# CCjammerRev2_TOP.net
KiCad netlist of a schematic drawn in Altium Designer
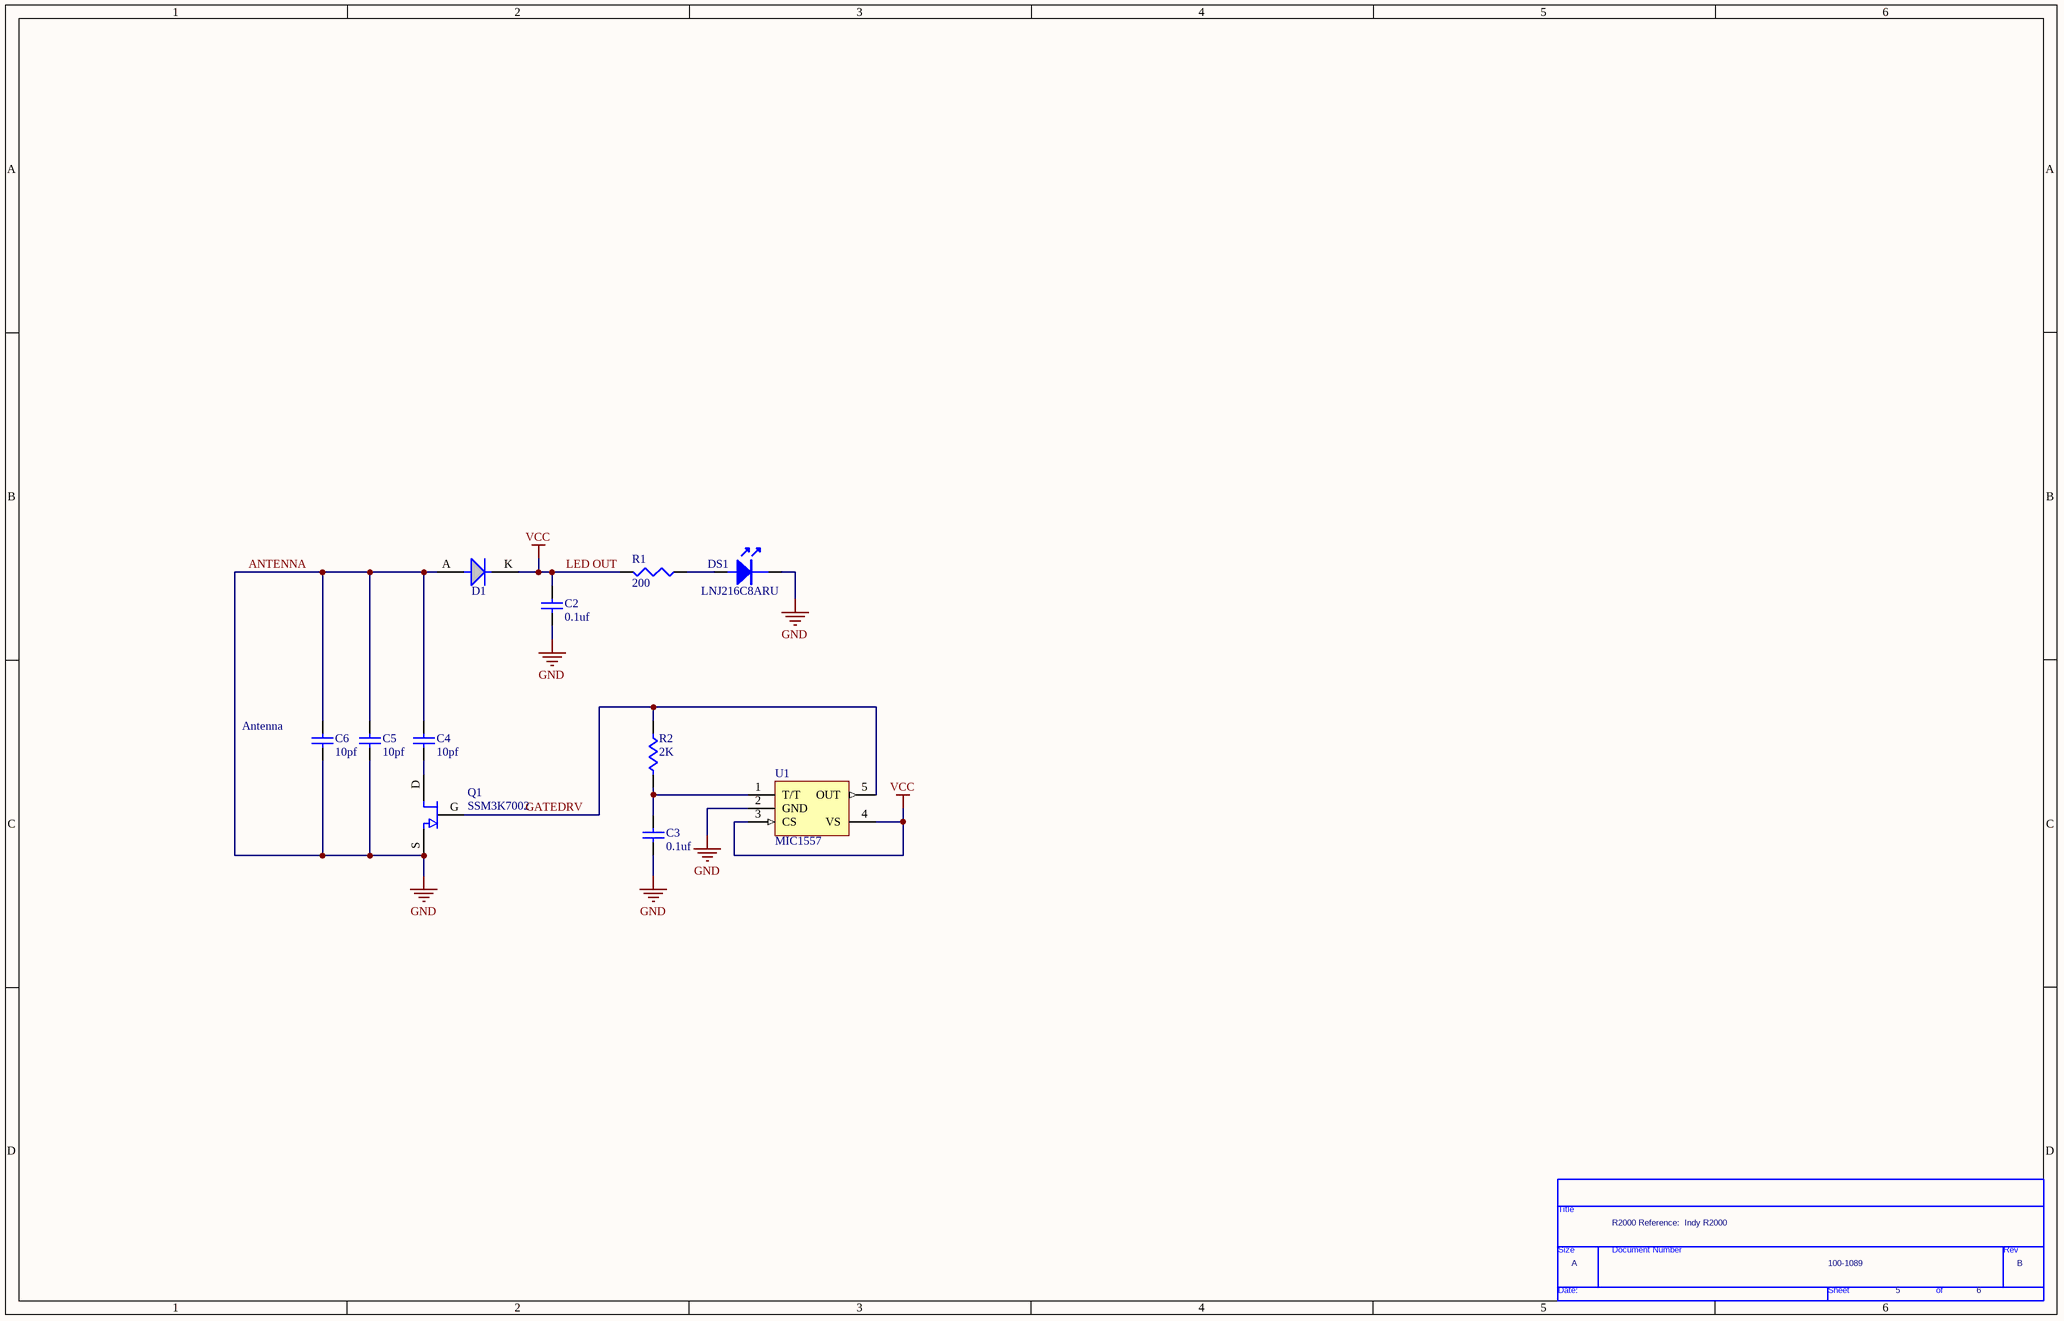
[diagram p0: CCjammerRev2_TOP.SchDoc]

(export (version "E")
  (design (tool "Eeschema 10.0.6"))
  (components
    (comp (ref "*")
      (value "TitleBlock0")
      (fields
        (field (name "PAGE COUNT") "6")
        (field (name "PAGE NUMBER") "5")
        (field (name "PAGE SIZE") "A")
        (field (name "TITLE") "R2000 Reference:  Indy R2000")
        (field (name "REVCODE") "B")
        (field (name "DOC") "100-1089")
      )
      (libsource (lib "*") (part "TitleBlock0"))
    )
    (comp (ref "C2")
      (value "0.1uf")
      (footprint "0603_072205")
      (description "Capacitor")
      (fields (field (name "PARTNO") "TMK212BJ475KG-T"))
      (libsource (lib "Miscellaneous Devices") (part "Cap"))
    )
    (comp (ref "C3")
      (value "0.1uf")
      (footprint "0603_072205")
      (description "Capacitor")
      (libsource (lib "Miscellaneous Devices") (part "Cap"))
    )
    (comp (ref "C4")
      (value "10pf")
      (footprint "0603_072205")
      (description "Capacitor")
      (libsource (lib "Miscellaneous Devices") (part "Cap"))
    )
    (comp (ref "C5")
      (value "10pf")
      (footprint "0603_072205")
      (description "Capacitor")
      (libsource (lib "Miscellaneous Devices") (part "Cap"))
    )
    (comp (ref "C6")
      (value "10pf")
      (footprint "0603_072205")
      (description "Capacitor")
      (libsource (lib "Miscellaneous Devices") (part "Cap"))
    )
    (comp (ref "D1")
      (value "Diode")
      (footprint "DIODE_FSC_091912")
      (fields (field (name "PARTNO") "1SS416(TL4D)TR-ND") (field (name "MFG") "Toshiba"))
      (libsource (lib "Common") (part "DIODE"))
    )
    (comp (ref "DS1")
      (value "LNJ216C8ARU")
      (footprint "Tag105 Rev20:404-1032-2-ND")
      (fields (field (name "MANUFACTURER") "Panasonic"))
      (libsource (lib "ActiveWave MasterLib") (part "LED"))
    )
    (comp (ref "Q1")
      (value "SSM3K7002")
      (footprint "SOT23 SMALL_FET_012005")
      (fields (field (name "PARTNO") "SSM3K7002BFU") (field (name "MFG") "Toshiba"))
      (libsource (lib "Common") (part "FET N CHANNEL"))
    )
    (comp (ref "R1")
      (value "200")
      (footprint "0603")
      (libsource (lib "ActiveWave MasterLib") (part "RES-0603"))
    )
    (comp (ref "R2")
      (value "2K")
      (footprint "0603_072205")
      (fields (field (name "PARTNO") "RES-0000"))
      (libsource (lib "Discrete") (part "RESISTOR"))
    )
    (comp (ref "U1")
      (value "MIC1557")
      (footprint "SOT25_030205")
      (fields (field (name "MFG") "Micrel") (field (name "PARTNO") "MIC1557YM5"))
      (libsource (lib "Common") (part "MIC1555"))
    )
  )
  (nets
    (net (code "1") (name "/GATEDRV") (class "Default")
      (node (ref "Q1") (pin "G") (pinfunction "G_G") (pintype "passive"))
      (node (ref "R2") (pin "2") (pinfunction "2_2") (pintype "passive"))
      (node (ref "U1") (pin "5") (pinfunction "OUT_5") (pintype "output"))
    )
    (net (code "2") (name "GND") (class "Default")
      (node (ref "C2") (pin "1") (pinfunction "1_1") (pintype "passive"))
      (node (ref "C3") (pin "1") (pinfunction "1_1") (pintype "passive"))
      (node (ref "C4") (pin "2") (pinfunction "2_2") (pintype "passive"))
      (node (ref "C5") (pin "1") (pinfunction "1_1") (pintype "passive"))
      (node (ref "C5") (pin "2") (pinfunction "2_2") (pintype "passive"))
      (node (ref "C6") (pin "1") (pinfunction "1_1") (pintype "passive"))
      (node (ref "C6") (pin "2") (pinfunction "2_2") (pintype "passive"))
      (node (ref "D1") (pin "A") (pinfunction "A_A") (pintype "passive"))
      (node (ref "DS1") (pin "K") (pinfunction "K_K") (pintype "passive"))
      (node (ref "Q1") (pin "S") (pinfunction "S_S") (pintype "passive"))
      (node (ref "U1") (pin "2") (pinfunction "GND_2") (pintype "power_in"))
    )
    (net (code "3") (name "Net-(C4-Pad1)") (class "Default")
      (node (ref "C4") (pin "1") (pinfunction "1_1") (pintype "passive"))
      (node (ref "Q1") (pin "D") (pinfunction "D_D") (pintype "passive"))
    )
    (net (code "4") (name "Net-(DS1-PadA)") (class "Default")
      (node (ref "DS1") (pin "A") (pinfunction "A_A") (pintype "passive"))
      (node (ref "R1") (pin "1") (pinfunction "1_1") (pintype "passive"))
    )
    (net (code "5") (name "Net-(U1-T{slash}T)") (class "Default")
      (node (ref "C3") (pin "2") (pinfunction "2_2") (pintype "passive"))
      (node (ref "R2") (pin "1") (pinfunction "1_1") (pintype "passive"))
      (node (ref "U1") (pin "1") (pinfunction "T/T_1") (pintype "passive"))
    )
    (net (code "6") (name "VCC") (class "Default")
      (node (ref "C2") (pin "2") (pinfunction "2_2") (pintype "passive"))
      (node (ref "D1") (pin "K") (pinfunction "K_K") (pintype "passive"))
      (node (ref "R1") (pin "2") (pinfunction "2_2") (pintype "passive"))
      (node (ref "U1") (pin "3") (pinfunction "CS_3") (pintype "input"))
      (node (ref "U1") (pin "4") (pinfunction "VS_4") (pintype "power_in"))
    )
  )
)
